# giro.net
KiCad netlist of a schematic drawn in Altium Designer
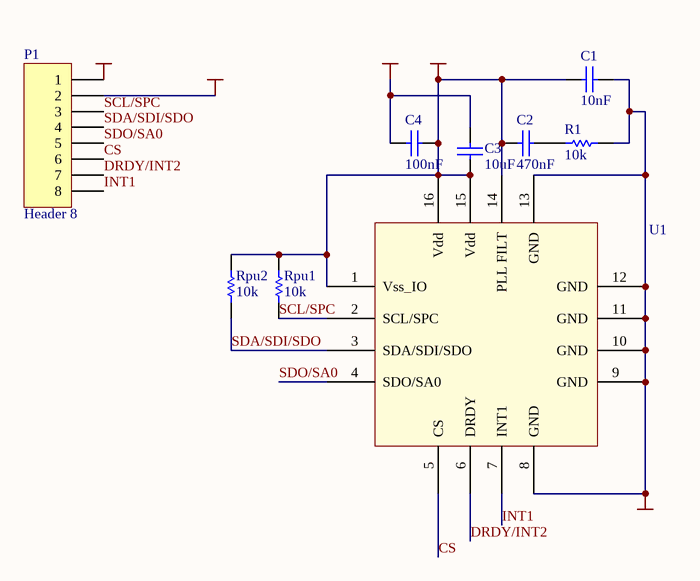
[diagram p0: giro.SchDoc]

(export (version "E")
  (design (tool "Eeschema 10.0.6"))
  (components
    (comp (ref "C1")
      (value "10nF")
      (footprint "L3G4200D:0603")
      (description "Capacitor")
      (fields (field (name "PUBLISHER") "Altium Limited"))
      (libsource (lib "Miscellaneous Devices") (part "Cap"))
    )
    (comp (ref "C2")
      (value "470nF")
      (footprint "L3G4200D:0603")
      (description "Capacitor")
      (fields (field (name "PUBLISHER") "Altium Limited"))
      (libsource (lib "Miscellaneous Devices") (part "Cap"))
    )
    (comp (ref "C3")
      (value "10uF")
      (description "Capacitor")
      (fields (field (name "PUBLISHER") "Altium Limited"))
      (libsource (lib "Miscellaneous Devices") (part "Cap"))
    )
    (comp (ref "C4")
      (value "100nF")
      (description "Capacitor")
      (fields (field (name "PUBLISHER") "Altium Limited"))
      (libsource (lib "Miscellaneous Devices") (part "Cap"))
    )
    (comp (ref "P1")
      (value "Header 8")
      (footprint "HDR1X8")
      (description "Header, 8-Pin")
      (fields (field (name "PUBLISHER") "Altium Limited"))
      (libsource (lib "Miscellaneous Connectors") (part "Header 8"))
    )
    (comp (ref "R1")
      (value "10k")
      (footprint "L3G4200D:0603")
      (description "Semiconductor Resistor")
      (fields (field (name "PUBLISHER") "Altium Limited"))
      (libsource (lib "Miscellaneous Devices") (part "Res Semi"))
    )
    (comp (ref "Rpu1")
      (value "10k")
      (footprint "L3G4200D:0603")
      (description "Semiconductor Resistor")
      (fields (field (name "PUBLISHER") "Altium Limited"))
      (libsource (lib "Miscellaneous Devices") (part "Res Semi"))
    )
    (comp (ref "Rpu2")
      (value "10k")
      (footprint "L3G4200D:0603")
      (description "Semiconductor Resistor")
      (fields (field (name "PUBLISHER") "Altium Limited"))
      (libsource (lib "Miscellaneous Devices") (part "Res Semi"))
    )
    (comp (ref "U1")
      (value "L3G4200D")
      (footprint "L3G4200D")
      (description "Giro 3 axis")
      (libsource (lib "ST_Giro") (part "L3G4200D"))
    )
  )
  (nets
    (net (code "1") (name "/CS") (class "Default")
      (node (ref "P1") (pin "6") (pinfunction "6_6") (pintype "passive"))
      (node (ref "U1") (pin "5") (pinfunction "CS_5") (pintype "passive"))
    )
    (net (code "2") (name "/DRDY{slash}INT2") (class "Default")
      (node (ref "P1") (pin "7") (pinfunction "7_7") (pintype "passive"))
      (node (ref "U1") (pin "6") (pinfunction "DRDY_6") (pintype "passive"))
    )
    (net (code "3") (name "/INT1") (class "Default")
      (node (ref "P1") (pin "8") (pinfunction "8_8") (pintype "passive"))
      (node (ref "U1") (pin "7") (pinfunction "INT1_7") (pintype "passive"))
    )
    (net (code "4") (name "/SCL{slash}SPC") (class "Default")
      (node (ref "P1") (pin "3") (pinfunction "3_3") (pintype "passive"))
      (node (ref "Rpu1") (pin "2") (pinfunction "2_2") (pintype "passive"))
      (node (ref "U1") (pin "2") (pinfunction "SCL/SPC_2") (pintype "passive"))
    )
    (net (code "5") (name "/SDA{slash}SDI{slash}SDO") (class "Default")
      (node (ref "P1") (pin "4") (pinfunction "4_4") (pintype "passive"))
      (node (ref "Rpu2") (pin "2") (pinfunction "2_2") (pintype "passive"))
      (node (ref "U1") (pin "3") (pinfunction "SDA/SDI/SDO_3") (pintype "passive"))
    )
    (net (code "6") (name "/SDO{slash}SA0") (class "Default")
      (node (ref "P1") (pin "5") (pinfunction "5_5") (pintype "passive"))
      (node (ref "U1") (pin "4") (pinfunction "SDO/SA0_4") (pintype "passive"))
    )
    (net (code "7") (name "GND") (class "Default")
      (node (ref "C1") (pin "1") (pinfunction "1_1") (pintype "passive"))
      (node (ref "C3") (pin "2") (pinfunction "2_2") (pintype "passive"))
      (node (ref "C4") (pin "2") (pinfunction "2_2") (pintype "passive"))
      (node (ref "P1") (pin "1") (pinfunction "1_1") (pintype "passive"))
      (node (ref "R1") (pin "2") (pinfunction "2_2") (pintype "passive"))
      (node (ref "U1") (pin "10") (pinfunction "GND_10") (pintype "passive"))
      (node (ref "U1") (pin "11") (pinfunction "GND_11") (pintype "passive"))
      (node (ref "U1") (pin "12") (pinfunction "GND_12") (pintype "passive"))
      (node (ref "U1") (pin "13") (pinfunction "GND_13") (pintype "passive"))
      (node (ref "U1") (pin "8") (pinfunction "GND_8") (pintype "passive"))
      (node (ref "U1") (pin "9") (pinfunction "GND_9") (pintype "passive"))
    )
    (net (code "8") (name "Net-(C2-Pad2)") (class "Default")
      (node (ref "C2") (pin "2") (pinfunction "2_2") (pintype "passive"))
      (node (ref "R1") (pin "1") (pinfunction "1_1") (pintype "passive"))
    )
    (net (code "9") (name "VCC") (class "Default")
      (node (ref "C1") (pin "2") (pinfunction "2_2") (pintype "passive"))
      (node (ref "C2") (pin "1") (pinfunction "1_1") (pintype "passive"))
      (node (ref "C3") (pin "1") (pinfunction "1_1") (pintype "passive"))
      (node (ref "C4") (pin "1") (pinfunction "1_1") (pintype "passive"))
      (node (ref "P1") (pin "2") (pinfunction "2_2") (pintype "passive"))
      (node (ref "Rpu1") (pin "1") (pinfunction "1_1") (pintype "passive"))
      (node (ref "Rpu2") (pin "1") (pinfunction "1_1") (pintype "passive"))
      (node (ref "U1") (pin "1") (pinfunction "Vss_IO_1") (pintype "passive"))
      (node (ref "U1") (pin "14") (pinfunction "PLL_FILT_14") (pintype "passive"))
      (node (ref "U1") (pin "15") (pinfunction "Vdd_15") (pintype "passive"))
      (node (ref "U1") (pin "16") (pinfunction "Vdd_16") (pintype "passive"))
    )
  )
)
